# FLONW2WIQIA89IA.net
KiCad netlist of a schematic drawn in EAGLE
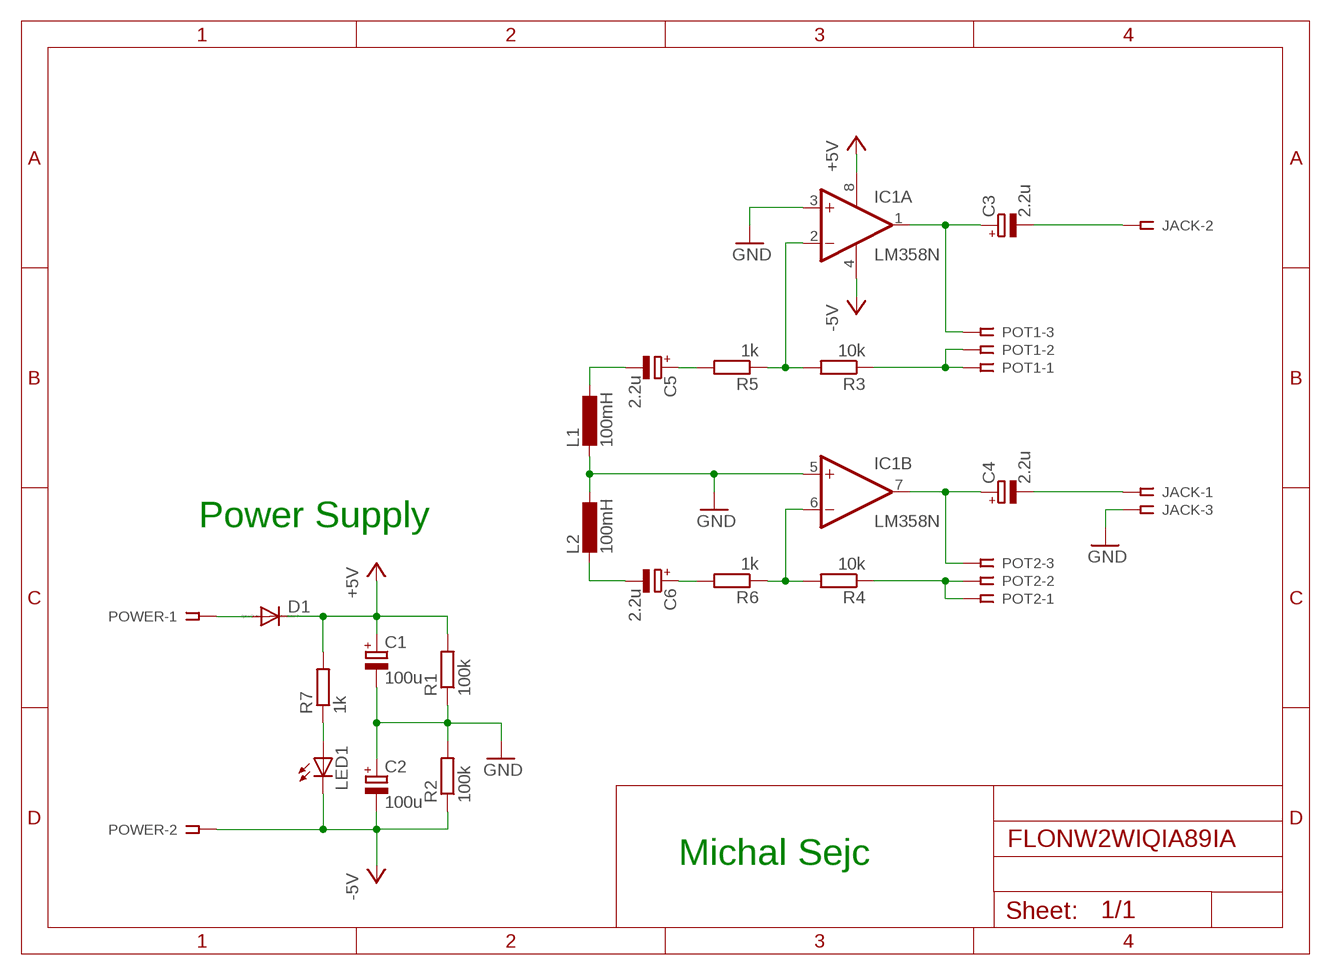
[diagram p0: schematic, sheet 1]

(export (version "E")
  (design (tool "Eeschema 10.0.6"))
  (components
    (comp (ref "C1")
      (value "100u")
      (footprint "eagle-import:E2,5-7")
      (libsource (lib "eagle-import") (part "CPOL-EUE2.5-7"))
    )
    (comp (ref "C2")
      (value "100u")
      (footprint "eagle-import:E2,5-7")
      (libsource (lib "eagle-import") (part "CPOL-EUE2.5-7"))
    )
    (comp (ref "C3")
      (value "2.2u")
      (footprint "eagle-import:E2,5-6E")
      (libsource (lib "eagle-import") (part "CPOL-EUE2,5-6E"))
    )
    (comp (ref "C4")
      (value "2.2u")
      (footprint "eagle-import:E2,5-6E")
      (libsource (lib "eagle-import") (part "CPOL-EUE2,5-6E"))
    )
    (comp (ref "C5")
      (value "2.2u")
      (footprint "eagle-import:E2,5-6E")
      (libsource (lib "eagle-import") (part "CPOL-EUE2,5-6E"))
    )
    (comp (ref "C6")
      (value "2.2u")
      (footprint "eagle-import:E2,5-6E")
      (libsource (lib "eagle-import") (part "CPOL-EUE2,5-6E"))
    )
    (comp (ref "D1")
      (value "1N4148DO35-7")
      (footprint "eagle-import:DO35-7")
      (libsource (lib "eagle-import") (part "1N4148DO35-7"))
    )
    (comp (ref "IC1")
      (value "LM358N")
      (footprint "eagle-import:DIL08")
      (libsource (lib "eagle-import") (part "LM358N"))
    )
    (comp (ref "JACK")
      (value "SSW-103-02-S-S-RA")
      (footprint "eagle-import:SSW-103-02-S-S-RA")
      (libsource (lib "eagle-import") (part "SSW-103-02-S-S-RA"))
    )
    (comp (ref "L1")
      (value "100mH")
      (footprint "eagle-import:0204_5")
      (libsource (lib "eagle-import") (part "L-EU0204/5"))
    )
    (comp (ref "L2")
      (value "100mH")
      (footprint "eagle-import:0204_5")
      (libsource (lib "eagle-import") (part "L-EU0204/5"))
    )
    (comp (ref "LED1")
      (value "LED5MM")
      (footprint "eagle-import:LED5MM")
      (libsource (lib "eagle-import") (part "LED5MM"))
    )
    (comp (ref "POT1")
      (value "SSW-103-02-S-S-RA")
      (footprint "eagle-import:SSW-103-02-S-S-RA")
      (libsource (lib "eagle-import") (part "SSW-103-02-S-S-RA"))
    )
    (comp (ref "POT2")
      (value "SSW-103-02-S-S-RA")
      (footprint "eagle-import:SSW-103-02-S-S-RA")
      (libsource (lib "eagle-import") (part "SSW-103-02-S-S-RA"))
    )
    (comp (ref "POWER")
      (value "SSW-102-02-S-S-RA")
      (footprint "eagle-import:SSW-102-02-S-S-RA")
      (libsource (lib "eagle-import") (part "SSW-102-02-S-S-RA"))
    )
    (comp (ref "R1")
      (value "100k")
      (footprint "eagle-import:0204_7")
      (libsource (lib "eagle-import") (part "R-EU_0204/7"))
    )
    (comp (ref "R2")
      (value "100k")
      (footprint "eagle-import:0204_7")
      (libsource (lib "eagle-import") (part "R-EU_0204/7"))
    )
    (comp (ref "R3")
      (value "10k")
      (footprint "eagle-import:0204_7")
      (libsource (lib "eagle-import") (part "R-EU_0204/7"))
    )
    (comp (ref "R4")
      (value "10k")
      (footprint "eagle-import:0204_7")
      (libsource (lib "eagle-import") (part "R-EU_0204/7"))
    )
    (comp (ref "R5")
      (value "1k")
      (footprint "eagle-import:0204_7")
      (libsource (lib "eagle-import") (part "R-EU_0204/7"))
    )
    (comp (ref "R6")
      (value "1k")
      (footprint "eagle-import:0204_7")
      (libsource (lib "eagle-import") (part "R-EU_0204/7"))
    )
    (comp (ref "R7")
      (value "1k")
      (footprint "eagle-import:0204_7")
      (libsource (lib "eagle-import") (part "R-EU_0204/7"))
    )
  )
  (nets
    (net (code "1") (name "+5V") (class "Default")
      (node (ref "C1") (pin "+") (pinfunction "+_+") (pintype "passive"))
      (node (ref "D1") (pin "C") (pinfunction "C_C") (pintype "passive"))
      (node (ref "IC1") (pin "8") (pinfunction "V+_8") (pintype "power_in"))
      (node (ref "R1") (pin "2") (pinfunction "2_2") (pintype "passive"))
      (node (ref "R7") (pin "2") (pinfunction "2_2") (pintype "passive"))
    )
    (net (code "2") (name "-5V") (class "Default")
      (node (ref "C2") (pin "-") (pinfunction "-_-") (pintype "passive"))
      (node (ref "IC1") (pin "4") (pinfunction "V-_4") (pintype "power_in"))
      (node (ref "LED1") (pin "K") (pinfunction "C_K") (pintype "passive"))
      (node (ref "POWER") (pin "2") (pinfunction "1_2") (pintype "passive"))
      (node (ref "R2") (pin "1") (pinfunction "1_1") (pintype "passive"))
    )
    (net (code "3") (name "GND") (class "Default")
      (node (ref "C1") (pin "-") (pinfunction "-_-") (pintype "passive"))
      (node (ref "C2") (pin "+") (pinfunction "+_+") (pintype "passive"))
      (node (ref "IC1") (pin "3") (pinfunction "+IN_3") (pintype "input"))
      (node (ref "IC1") (pin "5") (pinfunction "+IN_5") (pintype "input"))
      (node (ref "JACK") (pin "3") (pinfunction "1_3") (pintype "passive"))
      (node (ref "L1") (pin "2") (pinfunction "2_2") (pintype "passive"))
      (node (ref "L2") (pin "1") (pinfunction "1_1") (pintype "passive"))
      (node (ref "R1") (pin "1") (pinfunction "1_1") (pintype "passive"))
      (node (ref "R2") (pin "2") (pinfunction "2_2") (pintype "passive"))
    )
    (net (code "4") (name "Net-(C4-Pad-)") (class "Default")
      (node (ref "C4") (pin "-") (pinfunction "-_-") (pintype "passive"))
      (node (ref "JACK") (pin "1") (pinfunction "1_1") (pintype "passive"))
    )
    (net (code "5") (name "Net-(C5-Pad+)") (class "Default")
      (node (ref "C5") (pin "+") (pinfunction "+_+") (pintype "passive"))
      (node (ref "R5") (pin "2") (pinfunction "2_2") (pintype "passive"))
    )
    (net (code "6") (name "Net-(C5-Pad-)") (class "Default")
      (node (ref "C5") (pin "-") (pinfunction "-_-") (pintype "passive"))
      (node (ref "L1") (pin "1") (pinfunction "1_1") (pintype "passive"))
    )
    (net (code "7") (name "Net-(C6-Pad+)") (class "Default")
      (node (ref "C6") (pin "+") (pinfunction "+_+") (pintype "passive"))
      (node (ref "R6") (pin "2") (pinfunction "2_2") (pintype "passive"))
    )
    (net (code "8") (name "Net-(C6-Pad-)") (class "Default")
      (node (ref "C6") (pin "-") (pinfunction "-_-") (pintype "passive"))
      (node (ref "L2") (pin "2") (pinfunction "2_2") (pintype "passive"))
    )
    (net (code "9") (name "Net-(D1-PadA)") (class "Default")
      (node (ref "D1") (pin "A") (pinfunction "A_A") (pintype "passive"))
      (node (ref "POWER") (pin "1") (pinfunction "1_1") (pintype "passive"))
    )
    (net (code "10") (name "Net-(IC1A--IN)") (class "Default")
      (node (ref "IC1") (pin "2") (pinfunction "-IN_2") (pintype "input"))
      (node (ref "R3") (pin "2") (pinfunction "2_2") (pintype "passive"))
      (node (ref "R5") (pin "1") (pinfunction "1_1") (pintype "passive"))
    )
    (net (code "11") (name "Net-(IC1A-OUT)") (class "Default")
      (node (ref "C3") (pin "+") (pinfunction "+_+") (pintype "passive"))
      (node (ref "IC1") (pin "1") (pinfunction "OUT_1") (pintype "output"))
      (node (ref "POT1") (pin "3") (pinfunction "1_3") (pintype "passive"))
    )
    (net (code "12") (name "Net-(IC1B--IN)") (class "Default")
      (node (ref "IC1") (pin "6") (pinfunction "-IN_6") (pintype "input"))
      (node (ref "R4") (pin "2") (pinfunction "2_2") (pintype "passive"))
      (node (ref "R6") (pin "1") (pinfunction "1_1") (pintype "passive"))
    )
    (net (code "13") (name "Net-(IC1B-OUT)") (class "Default")
      (node (ref "C4") (pin "+") (pinfunction "+_+") (pintype "passive"))
      (node (ref "IC1") (pin "7") (pinfunction "OUT_7") (pintype "output"))
      (node (ref "POT2") (pin "3") (pinfunction "1_3") (pintype "passive"))
    )
    (net (code "14") (name "Net-(JACKB-1)") (class "Default")
      (node (ref "C3") (pin "-") (pinfunction "-_-") (pintype "passive"))
      (node (ref "JACK") (pin "2") (pinfunction "1_2") (pintype "passive"))
    )
    (net (code "15") (name "Net-(LED1-PadA)") (class "Default")
      (node (ref "LED1") (pin "A") (pinfunction "A_A") (pintype "passive"))
      (node (ref "R7") (pin "1") (pinfunction "1_1") (pintype "passive"))
    )
    (net (code "16") (name "Net-(POT1B-1)") (class "Default")
      (node (ref "POT1") (pin "1") (pinfunction "1_1") (pintype "passive"))
      (node (ref "POT1") (pin "2") (pinfunction "1_2") (pintype "passive"))
      (node (ref "R3") (pin "1") (pinfunction "1_1") (pintype "passive"))
    )
    (net (code "17") (name "Net-(POT2B-1)") (class "Default")
      (node (ref "POT2") (pin "1") (pinfunction "1_1") (pintype "passive"))
      (node (ref "POT2") (pin "2") (pinfunction "1_2") (pintype "passive"))
      (node (ref "R4") (pin "1") (pinfunction "1_1") (pintype "passive"))
    )
  )
)
